# V1_0.net
KiCad netlist of a schematic drawn in Altium Designer
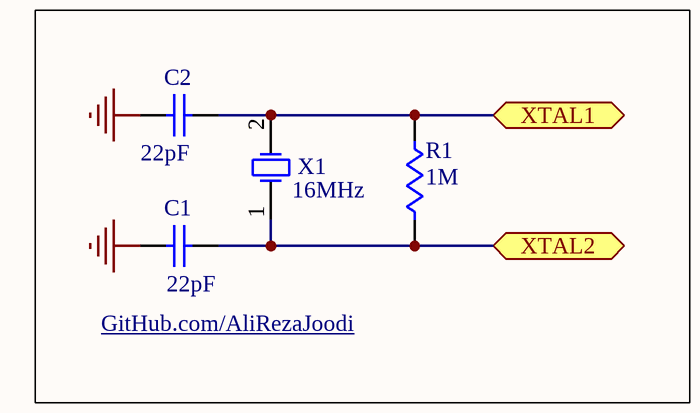
[diagram p0: V1.0.SchDoc]

(export (version "E")
  (design (tool "Eeschema 10.0.6"))
  (components
    (comp (ref "C1")
      (value "22pF")
      (footprint "CAPNTO2.54-3.05x1.78A")
      (description "Capacitor")
      (fields (field (name "MANUFACTURER") "Generic Components") (field (name "PUBLISHER") "Altium Limited"))
      (libsource (lib "Miscellaneous Devices") (part "Cap"))
    )
    (comp (ref "C2")
      (value "22pF")
      (footprint "CAPNTO2.54-3.05x1.78A")
      (description "Capacitor")
      (fields (field (name "MANUFACTURER") "Generic Components") (field (name "PUBLISHER") "Altium Limited"))
      (libsource (lib "Miscellaneous Devices") (part "Cap"))
    )
    (comp (ref "R1")
      (value "1M")
      (footprint "AXIAL-0.4")
      (description "Resistor")
      (fields (field (name "MANUFACTURER") "Generic Components") (field (name "PUBLISHER") "Altium Limited"))
      (libsource (lib "Miscellaneous Devices") (part "Res1"))
    )
    (comp (ref "X1")
      (value "16MHz")
      (footprint "XTAL_1")
      (description "Crystal Oscillator")
      (fields (field (name "MANUFACTURER") "Generic Components") (field (name "PUBLISHER") "Altium Limited"))
      (libsource (lib "Miscellaneous Devices") (part "XTAL"))
    )
  )
  (nets
    (net (code "1") (name "/XTAL1") (class "Default")
      (node (ref "C2") (pin "1") (pinfunction "1_1") (pintype "passive"))
      (node (ref "R1") (pin "2") (pinfunction "2_2") (pintype "passive"))
      (node (ref "X1") (pin "2") (pinfunction "OSC2_2") (pintype "passive"))
    )
    (net (code "2") (name "/XTAL2") (class "Default")
      (node (ref "C1") (pin "1") (pinfunction "1_1") (pintype "passive"))
      (node (ref "R1") (pin "1") (pinfunction "1_1") (pintype "passive"))
      (node (ref "X1") (pin "1") (pinfunction "OSC1_1") (pintype "passive"))
    )
    (net (code "3") (name "GND") (class "Default")
      (node (ref "C1") (pin "2") (pinfunction "2_2") (pintype "passive"))
      (node (ref "C2") (pin "2") (pinfunction "2_2") (pintype "passive"))
    )
  )
)
